# adapter.net
KiCad netlist of a schematic drawn in EAGLE
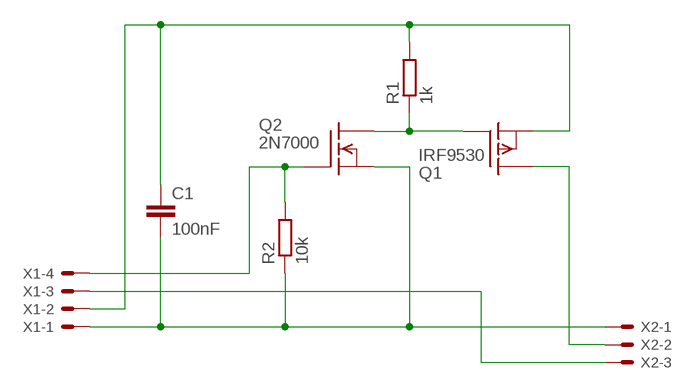
[diagram p0: schematic, sheet 1]

(export (version "E")
  (design (tool "Eeschema 10.0.6"))
  (components
    (comp (ref "C1")
      (value "100nF")
      (footprint "eagle-import:C050-030X075")
      (libsource (lib "eagle-import") (part "C-EU050-030X075"))
    )
    (comp (ref "Q1")
      (value "IRF9530")
      (footprint "eagle-import:TO220")
      (libsource (lib "eagle-import") (part "IRF9530"))
    )
    (comp (ref "Q2")
      (value "2N7000")
      (footprint "eagle-import:TO92")
      (libsource (lib "eagle-import") (part "BSS101"))
    )
    (comp (ref "R1")
      (value "1k")
      (footprint "eagle-import:0207_10")
      (libsource (lib "eagle-import") (part "R-EU_0207/10"))
    )
    (comp (ref "R2")
      (value "10k")
      (footprint "eagle-import:0207_10")
      (libsource (lib "eagle-import") (part "R-EU_0207/10"))
    )
    (comp (ref "X1")
      (value "KK-156-4")
      (footprint "eagle-import:KK-156-4")
      (libsource (lib "eagle-import") (part "KK-156-4"))
    )
    (comp (ref "X2")
      (value "KK-156-3")
      (footprint "eagle-import:KK-156-3")
      (libsource (lib "eagle-import") (part "KK-156-3"))
    )
  )
  (nets
    (net (code "1") (name "Net-(Q1-D)") (class "Default")
      (node (ref "Q1") (pin "2") (pinfunction "D_2") (pintype "passive"))
      (node (ref "X2") (pin "2") (pinfunction "S_2") (pintype "passive"))
    )
    (net (code "2") (name "Net-(Q1-G)") (class "Default")
      (node (ref "Q1") (pin "1") (pinfunction "G_1") (pintype "passive"))
      (node (ref "Q2") (pin "3") (pinfunction "D_3") (pintype "passive"))
      (node (ref "R1") (pin "1") (pinfunction "1_1") (pintype "passive"))
    )
    (net (code "3") (name "Net-(Q1-S)") (class "Default")
      (node (ref "C1") (pin "1") (pinfunction "1_1") (pintype "passive"))
      (node (ref "Q1") (pin "3") (pinfunction "S_3") (pintype "passive"))
      (node (ref "R1") (pin "2") (pinfunction "2_2") (pintype "passive"))
      (node (ref "X1") (pin "2") (pinfunction "S_2") (pintype "passive"))
    )
    (net (code "4") (name "Net-(Q2-G)") (class "Default")
      (node (ref "Q2") (pin "2") (pinfunction "G_2") (pintype "passive"))
      (node (ref "R2") (pin "2") (pinfunction "2_2") (pintype "passive"))
      (node (ref "X1") (pin "4") (pinfunction "S_4") (pintype "passive"))
    )
    (net (code "5") (name "Net-(Q2-S)") (class "Default")
      (node (ref "C1") (pin "2") (pinfunction "2_2") (pintype "passive"))
      (node (ref "Q2") (pin "1") (pinfunction "S_1") (pintype "passive"))
      (node (ref "R2") (pin "1") (pinfunction "1_1") (pintype "passive"))
      (node (ref "X1") (pin "1") (pinfunction "S_1") (pintype "passive"))
      (node (ref "X2") (pin "1") (pinfunction "S_1") (pintype "passive"))
    )
    (net (code "6") (name "Net-(X1C-S)") (class "Default")
      (node (ref "X1") (pin "3") (pinfunction "S_3") (pintype "passive"))
      (node (ref "X2") (pin "3") (pinfunction "S_3") (pintype "passive"))
    )
  )
)
